# button_sensor_side.net
KiCad netlist of a schematic drawn in EAGLE
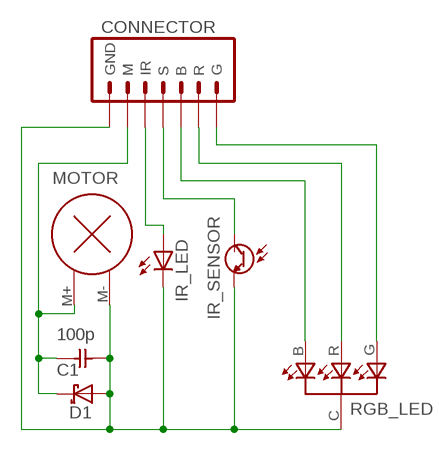
[diagram p0: schematic, sheet 1]

(export (version "E")
  (design (tool "Eeschema 10.0.6"))
  (components
    (comp (ref "C1")
      (value "100p")
      (footprint "eagle-import:C0805")
      (libsource (lib "eagle-import") (part "CAPACITORSMD_0805"))
    )
    (comp (ref "CONNECTOR")
      (value "CONNECTOR_PADS")
      (footprint "eagle-import:CONNECTOR_PADS")
      (libsource (lib "eagle-import") (part "CONNECTOR_PADS"))
    )
    (comp (ref "D1")
      (value "DIODE_SCHOTTKY")
      (footprint "eagle-import:NSR0530HT1G_SCHOTTKY_DIODE")
      (libsource (lib "eagle-import") (part "DIODE_SCHOTTKY"))
    )
    (comp (ref "IR_LED")
      (value "TCR5000_EMITTER")
      (footprint "eagle-import:TCR5000_IR_EMITTER")
      (libsource (lib "eagle-import") (part "TCR5000_EMITTER"))
    )
    (comp (ref "IR_SENSOR")
      (value "TCR5000_SENSOR")
      (footprint "eagle-import:TCR5000_IR_SENSOR")
      (libsource (lib "eagle-import") (part "TCR5000_SENSOR"))
    )
    (comp (ref "MOTOR")
      (value "VIBRATION_MOTOR")
      (footprint "eagle-import:VIBRATION_MOTOR")
      (libsource (lib "eagle-import") (part "VIBRATION_MOTOR"))
    )
    (comp (ref "RGB_LED")
      (value "APTF1616SEJ3ZGGVBDC_RBG_LED_SMT")
      (footprint "eagle-import:APTF1616SEJ3ZGGVBDC_RGB_LED_SMT")
      (libsource (lib "eagle-import") (part "APTF1616SEJ3ZGGVBDC_RBG_LED_SMT"))
    )
  )
  (nets
    (net (code "1") (name "Net-(CONNECTOR-PadIR)") (class "Default")
      (node (ref "CONNECTOR") (pin "IR") (pinfunction "IR_IR") (pintype "passive"))
      (node (ref "IR_LED") (pin "A") (pinfunction "A_A") (pintype "passive"))
    )
    (net (code "2") (name "Net-(CONNECTOR-PadS)") (class "Default")
      (node (ref "CONNECTOR") (pin "S") (pinfunction "S_S") (pintype "passive"))
      (node (ref "IR_SENSOR") (pin "C") (pinfunction "C_C") (pintype "passive"))
    )
    (net (code "3") (name "Net-(MOTOR-+)") (class "Default")
      (node (ref "C1") (pin "1") (pinfunction "1_1") (pintype "passive"))
      (node (ref "CONNECTOR") (pin "M") (pinfunction "M_M") (pintype "passive"))
      (node (ref "D1") (pin "C") (pinfunction "C_C") (pintype "passive"))
      (node (ref "MOTOR") (pin "M+") (pinfunction "+_M+") (pintype "bidirectional"))
    )
    (net (code "4") (name "Net-(MOTOR--)") (class "Default")
      (node (ref "C1") (pin "2") (pinfunction "2_2") (pintype "passive"))
      (node (ref "CONNECTOR") (pin "GND") (pinfunction "GND_GND") (pintype "passive"))
      (node (ref "CONNECTOR") (pin "GND_") (pinfunction "GND_GND_") (pintype "passive"))
      (node (ref "D1") (pin "A") (pinfunction "A_A") (pintype "passive"))
      (node (ref "IR_LED") (pin "C") (pinfunction "C_C") (pintype "passive"))
      (node (ref "IR_SENSOR") (pin "E") (pinfunction "E_E") (pintype "passive"))
      (node (ref "MOTOR") (pin "M-") (pinfunction "-_M-") (pintype "bidirectional"))
      (node (ref "RGB_LED") (pin "C") (pinfunction "C_C") (pintype "bidirectional"))
    )
    (net (code "5") (name "Net-(RGB_LED-BLUE)") (class "Default")
      (node (ref "CONNECTOR") (pin "B") (pinfunction "B_B") (pintype "passive"))
      (node (ref "RGB_LED") (pin "B") (pinfunction "BLUE_B") (pintype "passive"))
    )
    (net (code "6") (name "Net-(RGB_LED-GREEN)") (class "Default")
      (node (ref "CONNECTOR") (pin "G") (pinfunction "G_G") (pintype "passive"))
      (node (ref "RGB_LED") (pin "G") (pinfunction "GREEN_G") (pintype "passive"))
    )
    (net (code "7") (name "Net-(RGB_LED-RED)") (class "Default")
      (node (ref "CONNECTOR") (pin "R") (pinfunction "R_R") (pintype "passive"))
      (node (ref "RGB_LED") (pin "R") (pinfunction "RED_R") (pintype "passive"))
    )
  )
)
